# Example_Circuit.net
KiCad netlist of a schematic drawn in EAGLE
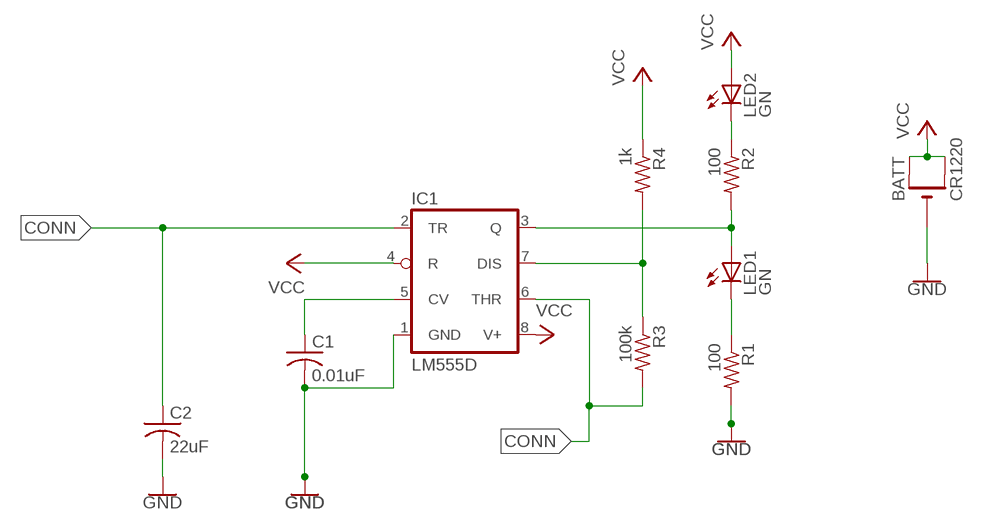
[diagram p0: schematic, sheet 1]

(export (version "E")
  (design (tool "Eeschema 10.0.6"))
  (components
    (comp (ref "BATT")
      (value "CR1220")
      (footprint "eagle-import:CR1220-SMD")
      (libsource (lib "eagle-import") (part "CR1220SMT"))
    )
    (comp (ref "C1")
      (value "0.01uF")
      (footprint "eagle-import:C0805")
      (fields (field (name "MF") "VISHAY/VITRAMON") (field (name "MPN") "VJ0805A103JXJTW1BC"))
      (libsource (lib "eagle-import") (part "C-USC0805"))
    )
    (comp (ref "C2")
      (value "22uF")
      (footprint "eagle-import:C0805")
      (fields (field (name "MPN") "C0805C226M8PACTU"))
      (libsource (lib "eagle-import") (part "C-USC0805"))
    )
    (comp (ref "IC1")
      (value "LM555D")
      (footprint "eagle-import:SO08")
      (fields (field (name "MF") "NATIONAL SEMICONDUCTOR") (field (name "MPN") "LMC555CM/NOPB"))
      (libsource (lib "eagle-import") (part "555DLM"))
    )
    (comp (ref "LED1")
      (value "GN")
      (footprint "eagle-import:CHIPLED_0805")
      (fields (field (name "MPN") "MCL-S270GC"))
      (libsource (lib "eagle-import") (part "LEDCHIPLED_0805"))
    )
    (comp (ref "LED2")
      (value "GN")
      (footprint "eagle-import:CHIPLED_0805")
      (fields (field (name "MPN") "MCL-S270GC"))
      (libsource (lib "eagle-import") (part "LEDCHIPLED_0805"))
    )
    (comp (ref "R1")
      (value "100")
      (footprint "eagle-import:R0805")
      (fields (field (name "MPN") "ERJ-3EKF1270V"))
      (libsource (lib "eagle-import") (part "R-US_R0805"))
    )
    (comp (ref "R2")
      (value "100")
      (footprint "eagle-import:R0805")
      (fields (field (name "MPN") "ERJ-3EKF1270V"))
      (libsource (lib "eagle-import") (part "R-US_R0805"))
    )
    (comp (ref "R3")
      (value "100k")
      (footprint "eagle-import:R0805")
      (fields (field (name "MPN") "CPF0805B100KE1"))
      (libsource (lib "eagle-import") (part "R-US_R0805"))
    )
    (comp (ref "R4")
      (value "1k")
      (footprint "eagle-import:R0805")
      (fields (field (name "MF") "VISHAY/DALE") (field (name "MPN") "CRCW04021K00FKTD"))
      (libsource (lib "eagle-import") (part "R-US_R0805"))
    )
  )
  (nets
    (net (code "1") (name "CONN") (class "Default")
      (node (ref "C2") (pin "1") (pinfunction "1_1") (pintype "passive"))
      (node (ref "IC1") (pin "2") (pinfunction "TR_2") (pintype "input"))
      (node (ref "IC1") (pin "6") (pinfunction "THR_6") (pintype "input"))
      (node (ref "R3") (pin "2") (pinfunction "2_2") (pintype "passive"))
    )
    (net (code "2") (name "GND") (class "Default")
      (node (ref "BATT") (pin "-") (pinfunction "-_-") (pintype "passive"))
      (node (ref "C1") (pin "2") (pinfunction "2_2") (pintype "passive"))
      (node (ref "C2") (pin "2") (pinfunction "2_2") (pintype "passive"))
      (node (ref "IC1") (pin "1") (pinfunction "GND_1") (pintype "power_in"))
      (node (ref "R1") (pin "2") (pinfunction "2_2") (pintype "passive"))
    )
    (net (code "3") (name "Net-(IC1-CV)") (class "Default")
      (node (ref "C1") (pin "1") (pinfunction "1_1") (pintype "passive"))
      (node (ref "IC1") (pin "5") (pinfunction "CV_5") (pintype "input"))
    )
    (net (code "4") (name "Net-(IC1-DIS)") (class "Default")
      (node (ref "IC1") (pin "7") (pinfunction "DIS_7") (pintype "input"))
      (node (ref "R3") (pin "1") (pinfunction "1_1") (pintype "passive"))
      (node (ref "R4") (pin "2") (pinfunction "2_2") (pintype "passive"))
    )
    (net (code "5") (name "Net-(IC1-Q)") (class "Default")
      (node (ref "IC1") (pin "3") (pinfunction "Q_3") (pintype "output"))
      (node (ref "LED1") (pin "A") (pinfunction "A_A") (pintype "passive"))
      (node (ref "R2") (pin "2") (pinfunction "2_2") (pintype "passive"))
    )
    (net (code "6") (name "Net-(LED1-PadC)") (class "Default")
      (node (ref "LED1") (pin "C") (pinfunction "C_C") (pintype "passive"))
      (node (ref "R1") (pin "1") (pinfunction "1_1") (pintype "passive"))
    )
    (net (code "7") (name "Net-(LED2-PadC)") (class "Default")
      (node (ref "LED2") (pin "C") (pinfunction "C_C") (pintype "passive"))
      (node (ref "R2") (pin "1") (pinfunction "1_1") (pintype "passive"))
    )
    (net (code "8") (name "VCC") (class "Default")
      (node (ref "BATT") (pin "+$1") (pinfunction "+_+$1") (pintype "passive"))
      (node (ref "BATT") (pin "+$2") (pinfunction "+1_+$2") (pintype "passive"))
      (node (ref "IC1") (pin "4") (pinfunction "R_4") (pintype "input"))
      (node (ref "IC1") (pin "8") (pinfunction "V+_8") (pintype "power_in"))
      (node (ref "LED2") (pin "A") (pinfunction "A_A") (pintype "passive"))
      (node (ref "R4") (pin "1") (pinfunction "1_1") (pintype "passive"))
    )
  )
)
